# open-race-scale-pi-zero-board-v_01.net
KiCad netlist of a schematic drawn in EAGLE
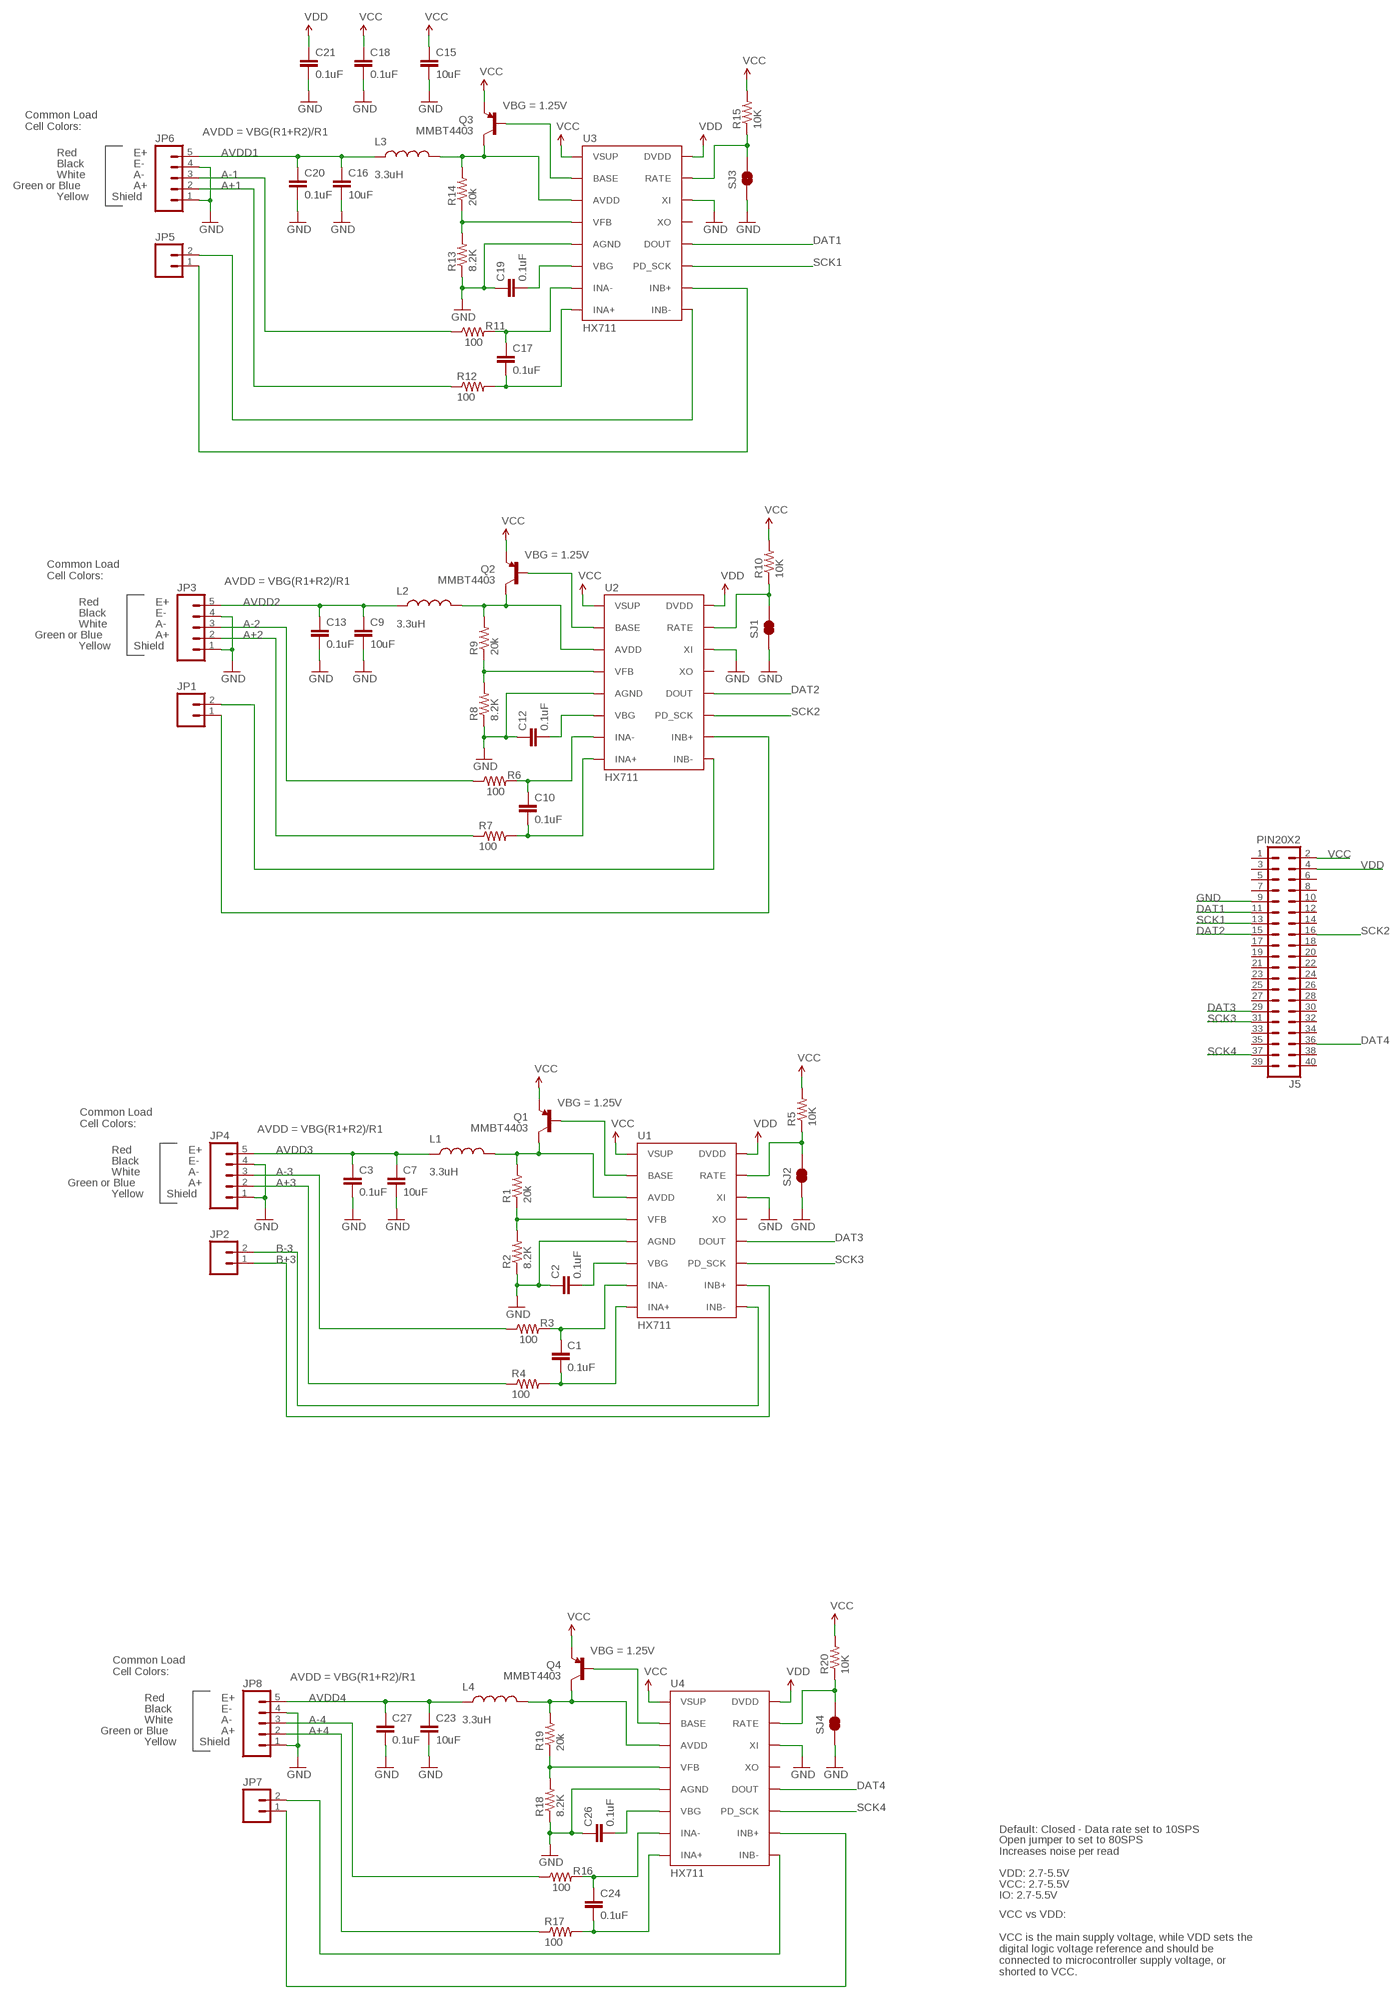
[diagram p0: schematic, sheet 1]

(export (version "E")
  (design (tool "Eeschema 10.0.6"))
  (components
    (comp (ref "C1")
      (value "0.1uF")
      (footprint "eagle-import:0603-CAP")
      (libsource (lib "eagle-import") (part "0.1UF-25V-5%(0603)"))
    )
    (comp (ref "C2")
      (value "0.1uF")
      (footprint "eagle-import:0603-CAP")
      (libsource (lib "eagle-import") (part "0.1UF-25V-5%(0603)"))
    )
    (comp (ref "C3")
      (value "0.1uF")
      (footprint "eagle-import:0603-CAP")
      (libsource (lib "eagle-import") (part "0.1UF-25V-5%(0603)"))
    )
    (comp (ref "C7")
      (value "10uF")
      (footprint "eagle-import:1210")
      (libsource (lib "eagle-import") (part "10UF50V20%(1210)"))
    )
    (comp (ref "C9")
      (value "10uF")
      (footprint "eagle-import:1210")
      (libsource (lib "eagle-import") (part "10UF50V20%(1210)"))
    )
    (comp (ref "C10")
      (value "0.1uF")
      (footprint "eagle-import:0603-CAP")
      (libsource (lib "eagle-import") (part "0.1UF-25V-5%(0603)"))
    )
    (comp (ref "C12")
      (value "0.1uF")
      (footprint "eagle-import:0603-CAP")
      (libsource (lib "eagle-import") (part "0.1UF-25V-5%(0603)"))
    )
    (comp (ref "C13")
      (value "0.1uF")
      (footprint "eagle-import:0603-CAP")
      (libsource (lib "eagle-import") (part "0.1UF-25V-5%(0603)"))
    )
    (comp (ref "C15")
      (value "10uF")
      (footprint "eagle-import:1210")
      (libsource (lib "eagle-import") (part "10UF50V20%(1210)"))
    )
    (comp (ref "C16")
      (value "10uF")
      (footprint "eagle-import:1210")
      (libsource (lib "eagle-import") (part "10UF50V20%(1210)"))
    )
    (comp (ref "C17")
      (value "0.1uF")
      (footprint "eagle-import:0603-CAP")
      (libsource (lib "eagle-import") (part "0.1UF-25V-5%(0603)"))
    )
    (comp (ref "C18")
      (value "0.1uF")
      (footprint "eagle-import:0603-CAP")
      (libsource (lib "eagle-import") (part "0.1UF-25V-5%(0603)"))
    )
    (comp (ref "C19")
      (value "0.1uF")
      (footprint "eagle-import:0603-CAP")
      (libsource (lib "eagle-import") (part "0.1UF-25V-5%(0603)"))
    )
    (comp (ref "C20")
      (value "0.1uF")
      (footprint "eagle-import:0603-CAP")
      (libsource (lib "eagle-import") (part "0.1UF-25V-5%(0603)"))
    )
    (comp (ref "C21")
      (value "0.1uF")
      (footprint "eagle-import:0603-CAP")
      (libsource (lib "eagle-import") (part "0.1UF-25V-5%(0603)"))
    )
    (comp (ref "C23")
      (value "10uF")
      (footprint "eagle-import:1210")
      (libsource (lib "eagle-import") (part "10UF50V20%(1210)"))
    )
    (comp (ref "C24")
      (value "0.1uF")
      (footprint "eagle-import:0603-CAP")
      (libsource (lib "eagle-import") (part "0.1UF-25V-5%(0603)"))
    )
    (comp (ref "C26")
      (value "0.1uF")
      (footprint "eagle-import:0603-CAP")
      (libsource (lib "eagle-import") (part "0.1UF-25V-5%(0603)"))
    )
    (comp (ref "C27")
      (value "0.1uF")
      (footprint "eagle-import:0603-CAP")
      (libsource (lib "eagle-import") (part "0.1UF-25V-5%(0603)"))
    )
    (comp (ref "J5")
      (value "PIN20X2")
      (footprint "eagle-import:PIN_20X2")
      (libsource (lib "eagle-import") (part "PIN20X2"))
    )
    (comp (ref "JP1")
      (value "M02PTH")
      (footprint "eagle-import:1X02")
      (libsource (lib "eagle-import") (part "M02PTH"))
    )
    (comp (ref "JP2")
      (value "M02PTH")
      (footprint "eagle-import:1X02")
      (libsource (lib "eagle-import") (part "M02PTH"))
    )
    (comp (ref "JP3")
      (value "M05PTH")
      (footprint "eagle-import:1X05")
      (libsource (lib "eagle-import") (part "M05PTH"))
    )
    (comp (ref "JP4")
      (value "M05PTH")
      (footprint "eagle-import:1X05")
      (libsource (lib "eagle-import") (part "M05PTH"))
    )
    (comp (ref "JP5")
      (value "M02PTH")
      (footprint "eagle-import:1X02")
      (libsource (lib "eagle-import") (part "M02PTH"))
    )
    (comp (ref "JP6")
      (value "M05PTH")
      (footprint "eagle-import:1X05")
      (libsource (lib "eagle-import") (part "M05PTH"))
    )
    (comp (ref "JP7")
      (value "M02PTH")
      (footprint "eagle-import:1X02")
      (libsource (lib "eagle-import") (part "M02PTH"))
    )
    (comp (ref "JP8")
      (value "M05PTH")
      (footprint "eagle-import:1X05")
      (libsource (lib "eagle-import") (part "M05PTH"))
    )
    (comp (ref "L1")
      (value "3.3uH")
      (footprint "eagle-import:0805")
      (libsource (lib "eagle-import") (part "INDUCTOR0805-IND"))
    )
    (comp (ref "L2")
      (value "3.3uH")
      (footprint "eagle-import:0805")
      (libsource (lib "eagle-import") (part "INDUCTOR0805-IND"))
    )
    (comp (ref "L3")
      (value "3.3uH")
      (footprint "eagle-import:0805")
      (libsource (lib "eagle-import") (part "INDUCTOR0805-IND"))
    )
    (comp (ref "L4")
      (value "3.3uH")
      (footprint "eagle-import:0805")
      (libsource (lib "eagle-import") (part "INDUCTOR0805-IND"))
    )
    (comp (ref "Q1")
      (value "MMBT4403")
      (footprint "eagle-import:SOT23-3")
      (libsource (lib "eagle-import") (part "TRANSISTOR_PNPMMBT4403"))
    )
    (comp (ref "Q2")
      (value "MMBT4403")
      (footprint "eagle-import:SOT23-3")
      (libsource (lib "eagle-import") (part "TRANSISTOR_PNPMMBT4403"))
    )
    (comp (ref "Q3")
      (value "MMBT4403")
      (footprint "eagle-import:SOT23-3")
      (libsource (lib "eagle-import") (part "TRANSISTOR_PNPMMBT4403"))
    )
    (comp (ref "Q4")
      (value "MMBT4403")
      (footprint "eagle-import:SOT23-3")
      (libsource (lib "eagle-import") (part "TRANSISTOR_PNPMMBT4403"))
    )
    (comp (ref "R1")
      (value "20k")
      (footprint "eagle-import:0603-RES")
      (libsource (lib "eagle-import") (part "20KOHM1/10W1%(0603)"))
    )
    (comp (ref "R2")
      (value "8.2K")
      (footprint "eagle-import:0603-RES")
      (libsource (lib "eagle-import") (part "8.2KOHM-1/10W-5%(0603)"))
    )
    (comp (ref "R3")
      (value "100")
      (footprint "eagle-import:0603-RES")
      (libsource (lib "eagle-import") (part "100OHM-1/10W-1%(0603)"))
    )
    (comp (ref "R4")
      (value "100")
      (footprint "eagle-import:0603-RES")
      (libsource (lib "eagle-import") (part "100OHM-1/10W-1%(0603)"))
    )
    (comp (ref "R5")
      (value "10K")
      (footprint "eagle-import:0603-RES")
      (libsource (lib "eagle-import") (part "10KOHM-1/10W-1%(0603)0603"))
    )
    (comp (ref "R6")
      (value "100")
      (footprint "eagle-import:0603-RES")
      (libsource (lib "eagle-import") (part "100OHM-1/10W-1%(0603)"))
    )
    (comp (ref "R7")
      (value "100")
      (footprint "eagle-import:0603-RES")
      (libsource (lib "eagle-import") (part "100OHM-1/10W-1%(0603)"))
    )
    (comp (ref "R8")
      (value "8.2K")
      (footprint "eagle-import:0603-RES")
      (libsource (lib "eagle-import") (part "8.2KOHM-1/10W-5%(0603)"))
    )
    (comp (ref "R9")
      (value "20k")
      (footprint "eagle-import:0603-RES")
      (libsource (lib "eagle-import") (part "20KOHM1/10W1%(0603)"))
    )
    (comp (ref "R10")
      (value "10K")
      (footprint "eagle-import:0603-RES")
      (libsource (lib "eagle-import") (part "10KOHM-1/10W-1%(0603)0603"))
    )
    (comp (ref "R11")
      (value "100")
      (footprint "eagle-import:0603-RES")
      (libsource (lib "eagle-import") (part "100OHM-1/10W-1%(0603)"))
    )
    (comp (ref "R12")
      (value "100")
      (footprint "eagle-import:0603-RES")
      (libsource (lib "eagle-import") (part "100OHM-1/10W-1%(0603)"))
    )
    (comp (ref "R13")
      (value "8.2K")
      (footprint "eagle-import:0603-RES")
      (libsource (lib "eagle-import") (part "8.2KOHM-1/10W-5%(0603)"))
    )
    (comp (ref "R14")
      (value "20k")
      (footprint "eagle-import:0603-RES")
      (libsource (lib "eagle-import") (part "20KOHM1/10W1%(0603)"))
    )
    (comp (ref "R15")
      (value "10K")
      (footprint "eagle-import:0603-RES")
      (libsource (lib "eagle-import") (part "10KOHM-1/10W-1%(0603)0603"))
    )
    (comp (ref "R16")
      (value "100")
      (footprint "eagle-import:0603-RES")
      (libsource (lib "eagle-import") (part "100OHM-1/10W-1%(0603)"))
    )
    (comp (ref "R17")
      (value "100")
      (footprint "eagle-import:0603-RES")
      (libsource (lib "eagle-import") (part "100OHM-1/10W-1%(0603)"))
    )
    (comp (ref "R18")
      (value "8.2K")
      (footprint "eagle-import:0603-RES")
      (libsource (lib "eagle-import") (part "8.2KOHM-1/10W-5%(0603)"))
    )
    (comp (ref "R19")
      (value "20k")
      (footprint "eagle-import:0603-RES")
      (libsource (lib "eagle-import") (part "20KOHM1/10W1%(0603)"))
    )
    (comp (ref "R20")
      (value "10K")
      (footprint "eagle-import:0603-RES")
      (libsource (lib "eagle-import") (part "10KOHM-1/10W-1%(0603)0603"))
    )
    (comp (ref "SJ1")
      (value "JUMPER-PAD-2-NC_BY_TRACE")
      (footprint "eagle-import:PAD-JUMPER-2-NC_BY_TRACE_YES_SILK")
      (libsource (lib "eagle-import") (part "JUMPER-PAD-2-NC_BY_TRACE"))
    )
    (comp (ref "SJ2")
      (value "JUMPER-PAD-2-NC_BY_TRACE")
      (footprint "eagle-import:PAD-JUMPER-2-NC_BY_TRACE_YES_SILK")
      (libsource (lib "eagle-import") (part "JUMPER-PAD-2-NC_BY_TRACE"))
    )
    (comp (ref "SJ3")
      (value "JUMPER-PAD-2-NC_BY_TRACE")
      (footprint "eagle-import:PAD-JUMPER-2-NC_BY_TRACE_YES_SILK")
      (libsource (lib "eagle-import") (part "JUMPER-PAD-2-NC_BY_TRACE"))
    )
    (comp (ref "SJ4")
      (value "JUMPER-PAD-2-NC_BY_TRACE")
      (footprint "eagle-import:PAD-JUMPER-2-NC_BY_TRACE_YES_SILK")
      (libsource (lib "eagle-import") (part "JUMPER-PAD-2-NC_BY_TRACE"))
    )
    (comp (ref "U1")
      (value "HX711")
      (footprint "eagle-import:SO16")
      (libsource (lib "eagle-import") (part "HX711HX711"))
    )
    (comp (ref "U2")
      (value "HX711")
      (footprint "eagle-import:SO16")
      (libsource (lib "eagle-import") (part "HX711HX711"))
    )
    (comp (ref "U3")
      (value "HX711")
      (footprint "eagle-import:SO16")
      (libsource (lib "eagle-import") (part "HX711HX711"))
    )
    (comp (ref "U4")
      (value "HX711")
      (footprint "eagle-import:SO16")
      (libsource (lib "eagle-import") (part "HX711HX711"))
    )
  )
  (nets
    (net (code "1") (name "/A+1") (class "Default")
      (node (ref "JP6") (pin "2") (pinfunction "2_2") (pintype "passive"))
      (node (ref "R12") (pin "1") (pinfunction "1_1") (pintype "passive"))
    )
    (net (code "2") (name "/A+2") (class "Default")
      (node (ref "JP3") (pin "2") (pinfunction "2_2") (pintype "passive"))
      (node (ref "R7") (pin "1") (pinfunction "1_1") (pintype "passive"))
    )
    (net (code "3") (name "/A+3") (class "Default")
      (node (ref "JP4") (pin "2") (pinfunction "2_2") (pintype "passive"))
      (node (ref "R4") (pin "1") (pinfunction "1_1") (pintype "passive"))
    )
    (net (code "4") (name "/A+4") (class "Default")
      (node (ref "JP8") (pin "2") (pinfunction "2_2") (pintype "passive"))
      (node (ref "R17") (pin "1") (pinfunction "1_1") (pintype "passive"))
    )
    (net (code "5") (name "/A-1") (class "Default")
      (node (ref "JP6") (pin "3") (pinfunction "3_3") (pintype "passive"))
      (node (ref "R11") (pin "1") (pinfunction "1_1") (pintype "passive"))
    )
    (net (code "6") (name "/A-2") (class "Default")
      (node (ref "JP3") (pin "3") (pinfunction "3_3") (pintype "passive"))
      (node (ref "R6") (pin "1") (pinfunction "1_1") (pintype "passive"))
    )
    (net (code "7") (name "/A-3") (class "Default")
      (node (ref "JP4") (pin "3") (pinfunction "3_3") (pintype "passive"))
      (node (ref "R3") (pin "1") (pinfunction "1_1") (pintype "passive"))
    )
    (net (code "8") (name "/A-4") (class "Default")
      (node (ref "JP8") (pin "3") (pinfunction "3_3") (pintype "passive"))
      (node (ref "R16") (pin "1") (pinfunction "1_1") (pintype "passive"))
    )
    (net (code "9") (name "/AVDD1") (class "Default")
      (node (ref "C16") (pin "1") (pinfunction "1_1") (pintype "passive"))
      (node (ref "C20") (pin "1") (pinfunction "1_1") (pintype "passive"))
      (node (ref "JP6") (pin "5") (pinfunction "5_5") (pintype "passive"))
      (node (ref "L3") (pin "1") (pinfunction "1_1") (pintype "passive"))
    )
    (net (code "10") (name "/AVDD2") (class "Default")
      (node (ref "C13") (pin "1") (pinfunction "1_1") (pintype "passive"))
      (node (ref "C9") (pin "1") (pinfunction "1_1") (pintype "passive"))
      (node (ref "JP3") (pin "5") (pinfunction "5_5") (pintype "passive"))
      (node (ref "L2") (pin "1") (pinfunction "1_1") (pintype "passive"))
    )
    (net (code "11") (name "/AVDD3") (class "Default")
      (node (ref "C3") (pin "1") (pinfunction "1_1") (pintype "passive"))
      (node (ref "C7") (pin "1") (pinfunction "1_1") (pintype "passive"))
      (node (ref "JP4") (pin "5") (pinfunction "5_5") (pintype "passive"))
      (node (ref "L1") (pin "1") (pinfunction "1_1") (pintype "passive"))
    )
    (net (code "12") (name "/AVDD4") (class "Default")
      (node (ref "C23") (pin "1") (pinfunction "1_1") (pintype "passive"))
      (node (ref "C27") (pin "1") (pinfunction "1_1") (pintype "passive"))
      (node (ref "JP8") (pin "5") (pinfunction "5_5") (pintype "passive"))
      (node (ref "L4") (pin "1") (pinfunction "1_1") (pintype "passive"))
    )
    (net (code "13") (name "/B+3") (class "Default")
      (node (ref "JP2") (pin "1") (pinfunction "1_1") (pintype "passive"))
      (node (ref "U1") (pin "10") (pinfunction "INB+_10") (pintype "bidirectional"))
    )
    (net (code "14") (name "/B-3") (class "Default")
      (node (ref "JP2") (pin "2") (pinfunction "2_2") (pintype "passive"))
      (node (ref "U1") (pin "9") (pinfunction "INB-_9") (pintype "bidirectional"))
    )
    (net (code "15") (name "/DAT1") (class "Default")
      (node (ref "J5") (pin "11") (pinfunction "11_11") (pintype "passive"))
      (node (ref "U3") (pin "12") (pinfunction "DOUT_12") (pintype "bidirectional"))
    )
    (net (code "16") (name "/DAT2") (class "Default")
      (node (ref "J5") (pin "15") (pinfunction "15_15") (pintype "passive"))
      (node (ref "U2") (pin "12") (pinfunction "DOUT_12") (pintype "bidirectional"))
    )
    (net (code "17") (name "/DAT3") (class "Default")
      (node (ref "J5") (pin "29") (pinfunction "29_29") (pintype "passive"))
      (node (ref "U1") (pin "12") (pinfunction "DOUT_12") (pintype "bidirectional"))
    )
    (net (code "18") (name "/DAT4") (class "Default")
      (node (ref "J5") (pin "36") (pinfunction "36_36") (pintype "passive"))
      (node (ref "U4") (pin "12") (pinfunction "DOUT_12") (pintype "bidirectional"))
    )
    (net (code "19") (name "/SCK1") (class "Default")
      (node (ref "J5") (pin "13") (pinfunction "13_13") (pintype "passive"))
      (node (ref "U3") (pin "11") (pinfunction "PD_SCK_11") (pintype "bidirectional"))
    )
    (net (code "20") (name "/SCK2") (class "Default")
      (node (ref "J5") (pin "16") (pinfunction "16_16") (pintype "passive"))
      (node (ref "U2") (pin "11") (pinfunction "PD_SCK_11") (pintype "bidirectional"))
    )
    (net (code "21") (name "/SCK3") (class "Default")
      (node (ref "J5") (pin "31") (pinfunction "31_31") (pintype "passive"))
      (node (ref "U1") (pin "11") (pinfunction "PD_SCK_11") (pintype "bidirectional"))
    )
    (net (code "22") (name "/SCK4") (class "Default")
      (node (ref "J5") (pin "37") (pinfunction "37_37") (pintype "passive"))
      (node (ref "U4") (pin "11") (pinfunction "PD_SCK_11") (pintype "bidirectional"))
    )
    (net (code "23") (name "GND") (class "Default")
      (node (ref "C12") (pin "1") (pinfunction "1_1") (pintype "passive"))
      (node (ref "C13") (pin "2") (pinfunction "2_2") (pintype "passive"))
      (node (ref "C15") (pin "2") (pinfunction "2_2") (pintype "passive"))
      (node (ref "C16") (pin "2") (pinfunction "2_2") (pintype "passive"))
      (node (ref "C18") (pin "2") (pinfunction "2_2") (pintype "passive"))
      (node (ref "C19") (pin "1") (pinfunction "1_1") (pintype "passive"))
      (node (ref "C2") (pin "1") (pinfunction "1_1") (pintype "passive"))
      (node (ref "C20") (pin "2") (pinfunction "2_2") (pintype "passive"))
      (node (ref "C21") (pin "2") (pinfunction "2_2") (pintype "passive"))
      (node (ref "C23") (pin "2") (pinfunction "2_2") (pintype "passive"))
      (node (ref "C26") (pin "1") (pinfunction "1_1") (pintype "passive"))
      (node (ref "C27") (pin "2") (pinfunction "2_2") (pintype "passive"))
      (node (ref "C3") (pin "2") (pinfunction "2_2") (pintype "passive"))
      (node (ref "C7") (pin "2") (pinfunction "2_2") (pintype "passive"))
      (node (ref "C9") (pin "2") (pinfunction "2_2") (pintype "passive"))
      (node (ref "J5") (pin "9") (pinfunction "9_9") (pintype "passive"))
      (node (ref "JP3") (pin "1") (pinfunction "1_1") (pintype "passive"))
      (node (ref "JP3") (pin "4") (pinfunction "4_4") (pintype "passive"))
      (node (ref "JP4") (pin "1") (pinfunction "1_1") (pintype "passive"))
      (node (ref "JP4") (pin "4") (pinfunction "4_4") (pintype "passive"))
      (node (ref "JP6") (pin "1") (pinfunction "1_1") (pintype "passive"))
      (node (ref "JP6") (pin "4") (pinfunction "4_4") (pintype "passive"))
      (node (ref "JP8") (pin "1") (pinfunction "1_1") (pintype "passive"))
      (node (ref "JP8") (pin "4") (pinfunction "4_4") (pintype "passive"))
      (node (ref "R13") (pin "1") (pinfunction "1_1") (pintype "passive"))
      (node (ref "R18") (pin "1") (pinfunction "1_1") (pintype "passive"))
      (node (ref "R2") (pin "1") (pinfunction "1_1") (pintype "passive"))
      (node (ref "R8") (pin "1") (pinfunction "1_1") (pintype "passive"))
      (node (ref "SJ1") (pin "1") (pinfunction "1_1") (pintype "passive"))
      (node (ref "SJ2") (pin "1") (pinfunction "1_1") (pintype "passive"))
      (node (ref "SJ3") (pin "1") (pinfunction "1_1") (pintype "passive"))
      (node (ref "SJ4") (pin "1") (pinfunction "1_1") (pintype "passive"))
      (node (ref "U1") (pin "14") (pinfunction "XI_14") (pintype "bidirectional"))
      (node (ref "U1") (pin "5") (pinfunction "AGND_5") (pintype "bidirectional"))
      (node (ref "U2") (pin "14") (pinfunction "XI_14") (pintype "bidirectional"))
      (node (ref "U2") (pin "5") (pinfunction "AGND_5") (pintype "bidirectional"))
      (node (ref "U3") (pin "14") (pinfunction "XI_14") (pintype "bidirectional"))
      (node (ref "U3") (pin "5") (pinfunction "AGND_5") (pintype "bidirectional"))
      (node (ref "U4") (pin "14") (pinfunction "XI_14") (pintype "bidirectional"))
      (node (ref "U4") (pin "5") (pinfunction "AGND_5") (pintype "bidirectional"))
    )
    (net (code "24") (name "Net-(Q1-B)") (class "Default")
      (node (ref "Q1") (pin "1") (pinfunction "B_1") (pintype "passive"))
      (node (ref "U1") (pin "2") (pinfunction "BASE_2") (pintype "bidirectional"))
    )
    (net (code "25") (name "Net-(Q1-C)") (class "Default")
      (node (ref "L1") (pin "2") (pinfunction "2_2") (pintype "passive"))
      (node (ref "Q1") (pin "3") (pinfunction "C_3") (pintype "passive"))
      (node (ref "R1") (pin "2") (pinfunction "2_2") (pintype "passive"))
      (node (ref "U1") (pin "3") (pinfunction "AVDD_3") (pintype "bidirectional"))
    )
    (net (code "26") (name "Net-(Q2-B)") (class "Default")
      (node (ref "Q2") (pin "1") (pinfunction "B_1") (pintype "passive"))
      (node (ref "U2") (pin "2") (pinfunction "BASE_2") (pintype "bidirectional"))
    )
    (net (code "27") (name "Net-(Q2-C)") (class "Default")
      (node (ref "L2") (pin "2") (pinfunction "2_2") (pintype "passive"))
      (node (ref "Q2") (pin "3") (pinfunction "C_3") (pintype "passive"))
      (node (ref "R9") (pin "2") (pinfunction "2_2") (pintype "passive"))
      (node (ref "U2") (pin "3") (pinfunction "AVDD_3") (pintype "bidirectional"))
    )
    (net (code "28") (name "Net-(Q3-B)") (class "Default")
      (node (ref "Q3") (pin "1") (pinfunction "B_1") (pintype "passive"))
      (node (ref "U3") (pin "2") (pinfunction "BASE_2") (pintype "bidirectional"))
    )
    (net (code "29") (name "Net-(Q3-C)") (class "Default")
      (node (ref "L3") (pin "2") (pinfunction "2_2") (pintype "passive"))
      (node (ref "Q3") (pin "3") (pinfunction "C_3") (pintype "passive"))
      (node (ref "R14") (pin "2") (pinfunction "2_2") (pintype "passive"))
      (node (ref "U3") (pin "3") (pinfunction "AVDD_3") (pintype "bidirectional"))
    )
    (net (code "30") (name "Net-(Q4-B)") (class "Default")
      (node (ref "Q4") (pin "1") (pinfunction "B_1") (pintype "passive"))
      (node (ref "U4") (pin "2") (pinfunction "BASE_2") (pintype "bidirectional"))
    )
    (net (code "31") (name "Net-(Q4-C)") (class "Default")
      (node (ref "L4") (pin "2") (pinfunction "2_2") (pintype "passive"))
      (node (ref "Q4") (pin "3") (pinfunction "C_3") (pintype "passive"))
      (node (ref "R19") (pin "2") (pinfunction "2_2") (pintype "passive"))
      (node (ref "U4") (pin "3") (pinfunction "AVDD_3") (pintype "bidirectional"))
    )
    (net (code "32") (name "Net-(U1-INA+)") (class "Default")
      (node (ref "C1") (pin "2") (pinfunction "2_2") (pintype "passive"))
      (node (ref "R4") (pin "2") (pinfunction "2_2") (pintype "passive"))
      (node (ref "U1") (pin "8") (pinfunction "INA+_8") (pintype "bidirectional"))
    )
    (net (code "33") (name "Net-(U1-INA-)") (class "Default")
      (node (ref "C1") (pin "1") (pinfunction "1_1") (pintype "passive"))
      (node (ref "R3") (pin "2") (pinfunction "2_2") (pintype "passive"))
      (node (ref "U1") (pin "7") (pinfunction "INA-_7") (pintype "bidirectional"))
    )
    (net (code "34") (name "Net-(U1-RATE)") (class "Default")
      (node (ref "R5") (pin "1") (pinfunction "1_1") (pintype "passive"))
      (node (ref "SJ2") (pin "2") (pinfunction "2_2") (pintype "passive"))
      (node (ref "U1") (pin "15") (pinfunction "RATE_15") (pintype "bidirectional"))
    )
    (net (code "35") (name "Net-(U1-VBG)") (class "Default")
      (node (ref "C2") (pin "2") (pinfunction "2_2") (pintype "passive"))
      (node (ref "U1") (pin "6") (pinfunction "VBG_6") (pintype "bidirectional"))
    )
    (net (code "36") (name "Net-(U1-VFB)") (class "Default")
      (node (ref "R1") (pin "1") (pinfunction "1_1") (pintype "passive"))
      (node (ref "R2") (pin "2") (pinfunction "2_2") (pintype "passive"))
      (node (ref "U1") (pin "4") (pinfunction "VFB_4") (pintype "bidirectional"))
    )
    (net (code "37") (name "Net-(U2-INA+)") (class "Default")
      (node (ref "C10") (pin "2") (pinfunction "2_2") (pintype "passive"))
      (node (ref "R7") (pin "2") (pinfunction "2_2") (pintype "passive"))
      (node (ref "U2") (pin "8") (pinfunction "INA+_8") (pintype "bidirectional"))
    )
    (net (code "38") (name "Net-(U2-INA-)") (class "Default")
      (node (ref "C10") (pin "1") (pinfunction "1_1") (pintype "passive"))
      (node (ref "R6") (pin "2") (pinfunction "2_2") (pintype "passive"))
      (node (ref "U2") (pin "7") (pinfunction "INA-_7") (pintype "bidirectional"))
    )
    (net (code "39") (name "Net-(U2-INB+)") (class "Default")
      (node (ref "JP1") (pin "1") (pinfunction "1_1") (pintype "passive"))
      (node (ref "U2") (pin "10") (pinfunction "INB+_10") (pintype "bidirectional"))
    )
    (net (code "40") (name "Net-(U2-INB-)") (class "Default")
      (node (ref "JP1") (pin "2") (pinfunction "2_2") (pintype "passive"))
      (node (ref "U2") (pin "9") (pinfunction "INB-_9") (pintype "bidirectional"))
    )
    (net (code "41") (name "Net-(U2-RATE)") (class "Default")
      (node (ref "R10") (pin "1") (pinfunction "1_1") (pintype "passive"))
      (node (ref "SJ1") (pin "2") (pinfunction "2_2") (pintype "passive"))
      (node (ref "U2") (pin "15") (pinfunction "RATE_15") (pintype "bidirectional"))
    )
    (net (code "42") (name "Net-(U2-VBG)") (class "Default")
      (node (ref "C12") (pin "2") (pinfunction "2_2") (pintype "passive"))
      (node (ref "U2") (pin "6") (pinfunction "VBG_6") (pintype "bidirectional"))
    )
    (net (code "43") (name "Net-(U2-VFB)") (class "Default")
      (node (ref "R8") (pin "2") (pinfunction "2_2") (pintype "passive"))
      (node (ref "R9") (pin "1") (pinfunction "1_1") (pintype "passive"))
      (node (ref "U2") (pin "4") (pinfunction "VFB_4") (pintype "bidirectional"))
    )
    (net (code "44") (name "Net-(U3-INA+)") (class "Default")
      (node (ref "C17") (pin "2") (pinfunction "2_2") (pintype "passive"))
      (node (ref "R12") (pin "2") (pinfunction "2_2") (pintype "passive"))
      (node (ref "U3") (pin "8") (pinfunction "INA+_8") (pintype "bidirectional"))
    )
    (net (code "45") (name "Net-(U3-INA-)") (class "Default")
      (node (ref "C17") (pin "1") (pinfunction "1_1") (pintype "passive"))
      (node (ref "R11") (pin "2") (pinfunction "2_2") (pintype "passive"))
      (node (ref "U3") (pin "7") (pinfunction "INA-_7") (pintype "bidirectional"))
    )
    (net (code "46") (name "Net-(U3-INB+)") (class "Default")
      (node (ref "JP5") (pin "1") (pinfunction "1_1") (pintype "passive"))
      (node (ref "U3") (pin "10") (pinfunction "INB+_10") (pintype "bidirectional"))
    )
    (net (code "47") (name "Net-(U3-INB-)") (class "Default")
      (node (ref "JP5") (pin "2") (pinfunction "2_2") (pintype "passive"))
      (node (ref "U3") (pin "9") (pinfunction "INB-_9") (pintype "bidirectional"))
    )
    (net (code "48") (name "Net-(U3-RATE)") (class "Default")
      (node (ref "R15") (pin "1") (pinfunction "1_1") (pintype "passive"))
      (node (ref "SJ3") (pin "2") (pinfunction "2_2") (pintype "passive"))
      (node (ref "U3") (pin "15") (pinfunction "RATE_15") (pintype "bidirectional"))
    )
    (net (code "49") (name "Net-(U3-VBG)") (class "Default")
      (node (ref "C19") (pin "2") (pinfunction "2_2") (pintype "passive"))
      (node (ref "U3") (pin "6") (pinfunction "VBG_6") (pintype "bidirectional"))
    )
    (net (code "50") (name "Net-(U3-VFB)") (class "Default")
      (node (ref "R13") (pin "2") (pinfunction "2_2") (pintype "passive"))
      (node (ref "R14") (pin "1") (pinfunction "1_1") (pintype "passive"))
      (node (ref "U3") (pin "4") (pinfunction "VFB_4") (pintype "bidirectional"))
    )
    (net (code "51") (name "Net-(U4-INA+)") (class "Default")
      (node (ref "C24") (pin "2") (pinfunction "2_2") (pintype "passive"))
      (node (ref "R17") (pin "2") (pinfunction "2_2") (pintype "passive"))
      (node (ref "U4") (pin "8") (pinfunction "INA+_8") (pintype "bidirectional"))
    )
    (net (code "52") (name "Net-(U4-INA-)") (class "Default")
      (node (ref "C24") (pin "1") (pinfunction "1_1") (pintype "passive"))
      (node (ref "R16") (pin "2") (pinfunction "2_2") (pintype "passive"))
      (node (ref "U4") (pin "7") (pinfunction "INA-_7") (pintype "bidirectional"))
    )
    (net (code "53") (name "Net-(U4-INB+)") (class "Default")
      (node (ref "JP7") (pin "1") (pinfunction "1_1") (pintype "passive"))
      (node (ref "U4") (pin "10") (pinfunction "INB+_10") (pintype "bidirectional"))
    )
    (net (code "54") (name "Net-(U4-INB-)") (class "Default")
      (node (ref "JP7") (pin "2") (pinfunction "2_2") (pintype "passive"))
      (node (ref "U4") (pin "9") (pinfunction "INB-_9") (pintype "bidirectional"))
    )
    (net (code "55") (name "Net-(U4-RATE)") (class "Default")
      (node (ref "R20") (pin "1") (pinfunction "1_1") (pintype "passive"))
      (node (ref "SJ4") (pin "2") (pinfunction "2_2") (pintype "passive"))
      (node (ref "U4") (pin "15") (pinfunction "RATE_15") (pintype "bidirectional"))
    )
    (net (code "56") (name "Net-(U4-VBG)") (class "Default")
      (node (ref "C26") (pin "2") (pinfunction "2_2") (pintype "passive"))
      (node (ref "U4") (pin "6") (pinfunction "VBG_6") (pintype "bidirectional"))
    )
    (net (code "57") (name "Net-(U4-VFB)") (class "Default")
      (node (ref "R18") (pin "2") (pinfunction "2_2") (pintype "passive"))
      (node (ref "R19") (pin "1") (pinfunction "1_1") (pintype "passive"))
      (node (ref "U4") (pin "4") (pinfunction "VFB_4") (pintype "bidirectional"))
    )
    (net (code "58") (name "VCC") (class "Default")
      (node (ref "C15") (pin "1") (pinfunction "1_1") (pintype "passive"))
      (node (ref "C18") (pin "1") (pinfunction "1_1") (pintype "passive"))
      (node (ref "J5") (pin "2") (pinfunction "2_2") (pintype "passive"))
      (node (ref "Q1") (pin "2") (pinfunction "E_2") (pintype "passive"))
      (node (ref "Q2") (pin "2") (pinfunction "E_2") (pintype "passive"))
      (node (ref "Q3") (pin "2") (pinfunction "E_2") (pintype "passive"))
      (node (ref "Q4") (pin "2") (pinfunction "E_2") (pintype "passive"))
      (node (ref "R10") (pin "2") (pinfunction "2_2") (pintype "passive"))
      (node (ref "R15") (pin "2") (pinfunction "2_2") (pintype "passive"))
      (node (ref "R20") (pin "2") (pinfunction "2_2") (pintype "passive"))
      (node (ref "R5") (pin "2") (pinfunction "2_2") (pintype "passive"))
      (node (ref "U1") (pin "1") (pinfunction "VSUP_1") (pintype "bidirectional"))
      (node (ref "U2") (pin "1") (pinfunction "VSUP_1") (pintype "bidirectional"))
      (node (ref "U3") (pin "1") (pinfunction "VSUP_1") (pintype "bidirectional"))
      (node (ref "U4") (pin "1") (pinfunction "VSUP_1") (pintype "bidirectional"))
    )
    (net (code "59") (name "VDD") (class "Default")
      (node (ref "C21") (pin "1") (pinfunction "1_1") (pintype "passive"))
      (node (ref "J5") (pin "4") (pinfunction "4_4") (pintype "passive"))
      (node (ref "U1") (pin "16") (pinfunction "DVDD_16") (pintype "bidirectional"))
      (node (ref "U2") (pin "16") (pinfunction "DVDD_16") (pintype "bidirectional"))
      (node (ref "U3") (pin "16") (pinfunction "DVDD_16") (pintype "bidirectional"))
      (node (ref "U4") (pin "16") (pinfunction "DVDD_16") (pintype "bidirectional"))
    )
    (net (code "60") (name "unconnected-(J5-Pad1)") (class "Default")
      (node (ref "J5") (pin "1") (pinfunction "1_1") (pintype "passive"))
    )
    (net (code "61") (name "unconnected-(J5-Pad3)") (class "Default")
      (node (ref "J5") (pin "3") (pinfunction "3_3") (pintype "passive"))
    )
    (net (code "62") (name "unconnected-(J5-Pad5)") (class "Default")
      (node (ref "J5") (pin "5") (pinfunction "5_5") (pintype "passive"))
    )
    (net (code "63") (name "unconnected-(J5-Pad6)") (class "Default")
      (node (ref "J5") (pin "6") (pinfunction "6_6") (pintype "passive"))
    )
    (net (code "64") (name "unconnected-(J5-Pad7)") (class "Default")
      (node (ref "J5") (pin "7") (pinfunction "7_7") (pintype "passive"))
    )
    (net (code "65") (name "unconnected-(J5-Pad8)") (class "Default")
      (node (ref "J5") (pin "8") (pinfunction "8_8") (pintype "passive"))
    )
    (net (code "66") (name "unconnected-(J5-Pad10)") (class "Default")
      (node (ref "J5") (pin "10") (pinfunction "10_10") (pintype "passive"))
    )
    (net (code "67") (name "unconnected-(J5-Pad12)") (class "Default")
      (node (ref "J5") (pin "12") (pinfunction "12_12") (pintype "passive"))
    )
    (net (code "68") (name "unconnected-(J5-Pad14)") (class "Default")
      (node (ref "J5") (pin "14") (pinfunction "14_14") (pintype "passive"))
    )
    (net (code "69") (name "unconnected-(J5-Pad17)") (class "Default")
      (node (ref "J5") (pin "17") (pinfunction "17_17") (pintype "passive"))
    )
    (net (code "70") (name "unconnected-(J5-Pad18)") (class "Default")
      (node (ref "J5") (pin "18") (pinfunction "18_18") (pintype "passive"))
    )
    (net (code "71") (name "unconnected-(J5-Pad19)") (class "Default")
      (node (ref "J5") (pin "19") (pinfunction "19_19") (pintype "passive"))
    )
    (net (code "72") (name "unconnected-(J5-Pad20)") (class "Default")
      (node (ref "J5") (pin "20") (pinfunction "20_20") (pintype "passive"))
    )
    (net (code "73") (name "unconnected-(J5-Pad21)") (class "Default")
      (node (ref "J5") (pin "21") (pinfunction "21_21") (pintype "passive"))
    )
    (net (code "74") (name "unconnected-(J5-Pad22)") (class "Default")
      (node (ref "J5") (pin "22") (pinfunction "22_22") (pintype "passive"))
    )
    (net (code "75") (name "unconnected-(J5-Pad23)") (class "Default")
      (node (ref "J5") (pin "23") (pinfunction "23_23") (pintype "passive"))
    )
    (net (code "76") (name "unconnected-(J5-Pad24)") (class "Default")
      (node (ref "J5") (pin "24") (pinfunction "24_24") (pintype "passive"))
    )
    (net (code "77") (name "unconnected-(J5-Pad25)") (class "Default")
      (node (ref "J5") (pin "25") (pinfunction "25_25") (pintype "passive"))
    )
    (net (code "78") (name "unconnected-(J5-Pad26)") (class "Default")
      (node (ref "J5") (pin "26") (pinfunction "26_26") (pintype "passive"))
    )
    (net (code "79") (name "unconnected-(J5-Pad27)") (class "Default")
      (node (ref "J5") (pin "27") (pinfunction "27_27") (pintype "passive"))
    )
    (net (code "80") (name "unconnected-(J5-Pad28)") (class "Default")
      (node (ref "J5") (pin "28") (pinfunction "28_28") (pintype "passive"))
    )
    (net (code "81") (name "unconnected-(J5-Pad30)") (class "Default")
      (node (ref "J5") (pin "30") (pinfunction "30_30") (pintype "passive"))
    )
    (net (code "82") (name "unconnected-(J5-Pad32)") (class "Default")
      (node (ref "J5") (pin "32") (pinfunction "32_32") (pintype "passive"))
    )
    (net (code "83") (name "unconnected-(J5-Pad33)") (class "Default")
      (node (ref "J5") (pin "33") (pinfunction "33_33") (pintype "passive"))
    )
    (net (code "84") (name "unconnected-(J5-Pad34)") (class "Default")
      (node (ref "J5") (pin "34") (pinfunction "34_34") (pintype "passive"))
    )
    (net (code "85") (name "unconnected-(J5-Pad35)") (class "Default")
      (node (ref "J5") (pin "35") (pinfunction "35_35") (pintype "passive"))
    )
    (net (code "86") (name "unconnected-(J5-Pad38)") (class "Default")
      (node (ref "J5") (pin "38") (pinfunction "38_38") (pintype "passive"))
    )
    (net (code "87") (name "unconnected-(J5-Pad39)") (class "Default")
      (node (ref "J5") (pin "39") (pinfunction "39_39") (pintype "passive"))
    )
    (net (code "88") (name "unconnected-(J5-Pad40)") (class "Default")
      (node (ref "J5") (pin "40") (pinfunction "40_40") (pintype "passive"))
    )
    (net (code "89") (name "unconnected-(U1-XO-Pad13)") (class "Default")
      (node (ref "U1") (pin "13") (pinfunction "XO_13") (pintype "bidirectional"))
    )
    (net (code "90") (name "unconnected-(U2-XO-Pad13)") (class "Default")
      (node (ref "U2") (pin "13") (pinfunction "XO_13") (pintype "bidirectional"))
    )
    (net (code "91") (name "unconnected-(U3-XO-Pad13)") (class "Default")
      (node (ref "U3") (pin "13") (pinfunction "XO_13") (pintype "bidirectional"))
    )
    (net (code "92") (name "unconnected-(U4-XO-Pad13)") (class "Default")
      (node (ref "U4") (pin "13") (pinfunction "XO_13") (pintype "bidirectional"))
    )
  )
)
